# 2019_TFT_Strateasy.net
KiCad netlist of a schematic drawn in Altium Designer
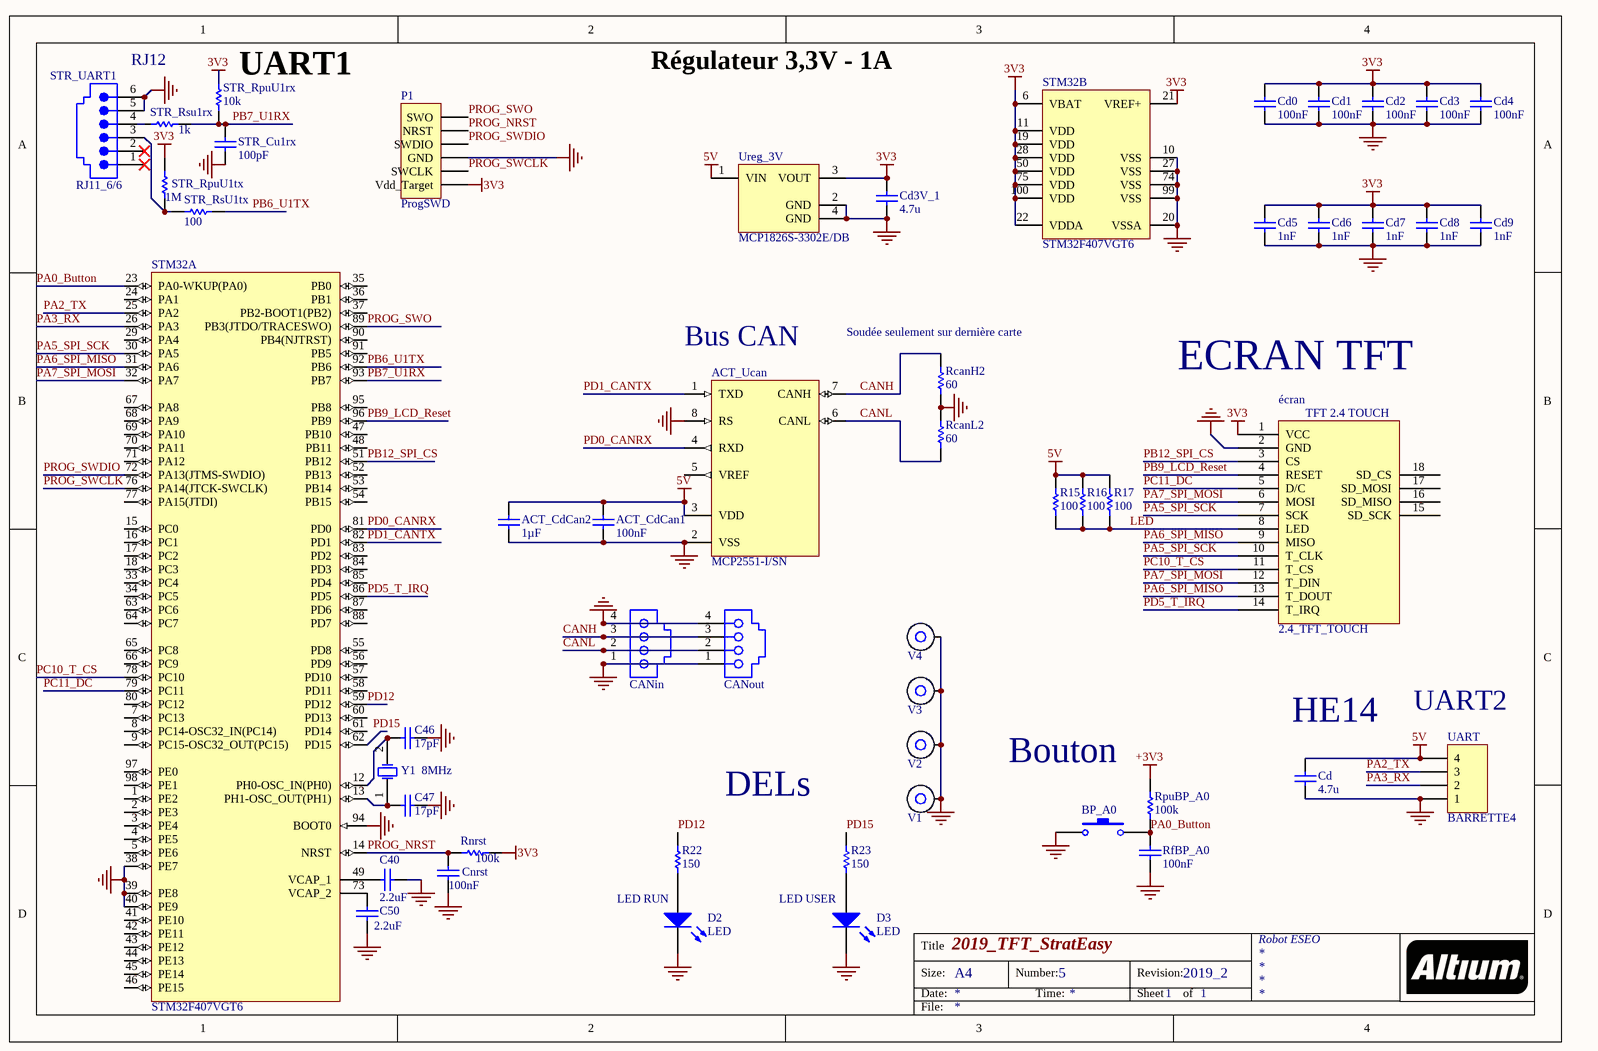
[diagram p0: 2019_TFT_Strateasy.SchDoc, left]
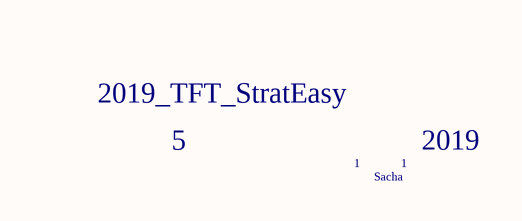
[diagram p1: 2019_TFT_Strateasy.SchDoc, right]

(export (version "E")
  (design (tool "Eeschema 10.0.6"))
  (components
    (comp (ref "ACT_CdCan1")
      (value "100nF")
      (footprint "C0805_N")
      (description "Capacitor")
      (fields (field (name "PUBLISHER") "Altium Limited"))
      (libsource (lib "_ROBOT") (part "Condensateur"))
    )
    (comp (ref "ACT_CdCan2")
      (value "1µF")
      (footprint "C0805_N")
      (description "Capacitor")
      (fields (field (name "PUBLISHER") "Altium Limited"))
      (libsource (lib "_ROBOT") (part "Condensateur"))
    )
    (comp (ref "ACT_Ucan")
      (value "MCP2551-I/SN")
      (footprint "SO8_N")
      (description "High-Speed CAN Transceiver, 8-Pin SOIC, Industrial Temperature")
      (fields (field (name "PUBLISHER") "Damien Guitton"))
      (libsource (lib "Circuit intégré") (part "MCP2551-I/SN"))
    )
    (comp (ref "BP_A0")
      (value "SW_Pushbutton_6x6mm_Vertical")
      (footprint "Switch 6x6 Vertical")
      (description "Switch tactil 6mm x 6mm Vertical")
      (fields (field (name "PUBLISHER") "Damien Guitton"))
      (libsource (lib "_ROBOT") (part "SW_Pushbutton_6x6mm_Vertical"))
    )
    (comp (ref "C40")
      (value "2.2uF")
      (footprint "C0805_N")
      (description "Capacitor")
      (fields (field (name "PUBLISHER") "Altium Limited"))
      (libsource (lib "_ROBOT") (part "Condensateur"))
    )
    (comp (ref "C46")
      (value "17pF")
      (footprint "C0805_N")
      (description "Capacitor")
      (fields (field (name "PUBLISHER") "Altium Limited"))
      (libsource (lib "_ROBOT") (part "Condensateur"))
    )
    (comp (ref "C47")
      (value "17pF")
      (footprint "C0805_N")
      (description "Capacitor")
      (fields (field (name "PUBLISHER") "Altium Limited"))
      (libsource (lib "_ROBOT") (part "Condensateur"))
    )
    (comp (ref "C50")
      (value "2.2uF")
      (footprint "C0805_N")
      (description "Capacitor")
      (fields (field (name "PUBLISHER") "Altium Limited"))
      (libsource (lib "_ROBOT") (part "Condensateur"))
    )
    (comp (ref "CANin")
      (value "634104149621")
      (footprint "634104149621")
      (description "Modular Jack SMT Vertical Plastic 4P4C Top Entry WR-MJ")
      (fields (field (name "PUBLISHER") "Wurth Elektronik"))
      (libsource (lib "ALTIUM-MJ_VERTICAL_PLASTIC") (part "634104149621"))
    )
    (comp (ref "CANout")
      (value "634104149621")
      (footprint "634104149621")
      (description "Modular Jack SMT Vertical Plastic 4P4C Top Entry WR-MJ")
      (fields (field (name "PUBLISHER") "Wurth Elektronik"))
      (libsource (lib "ALTIUM-MJ_VERTICAL_PLASTIC") (part "634104149621"))
    )
    (comp (ref "Cd")
      (value "4.7u")
      (footprint "C0805_N")
      (description "Capacitor")
      (fields (field (name "PUBLISHER") "Altium Limited"))
      (libsource (lib "_ROBOT") (part "Condensateur"))
    )
    (comp (ref "Cd0")
      (value "100nF")
      (footprint "C0805_N")
      (description "Capacitor")
      (fields (field (name "PUBLISHER") "Altium Limited"))
      (libsource (lib "_ROBOT") (part "Condensateur"))
    )
    (comp (ref "Cd1")
      (value "100nF")
      (footprint "C0805_N")
      (description "Capacitor")
      (fields (field (name "PUBLISHER") "Altium Limited"))
      (libsource (lib "_ROBOT") (part "Condensateur"))
    )
    (comp (ref "Cd2")
      (value "100nF")
      (footprint "C0805_N")
      (description "Capacitor")
      (fields (field (name "PUBLISHER") "Altium Limited"))
      (libsource (lib "_ROBOT") (part "Condensateur"))
    )
    (comp (ref "Cd3")
      (value "100nF")
      (footprint "C0805_N")
      (description "Capacitor")
      (fields (field (name "PUBLISHER") "Altium Limited"))
      (libsource (lib "_ROBOT") (part "Condensateur"))
    )
    (comp (ref "Cd3V_1")
      (value "4.7u")
      (footprint "C0805_N")
      (description "Capacitor")
      (fields (field (name "PUBLISHER") "Altium Limited"))
      (libsource (lib "DG_Condensateur") (part "Capacitor"))
    )
    (comp (ref "Cd4")
      (value "100nF")
      (footprint "C0805_N")
      (description "Capacitor")
      (fields (field (name "PUBLISHER") "Altium Limited"))
      (libsource (lib "_ROBOT") (part "Condensateur"))
    )
    (comp (ref "Cd5")
      (value "1nF")
      (footprint "C0805_N")
      (description "Capacitor")
      (fields (field (name "PUBLISHER") "Altium Limited"))
      (libsource (lib "_ROBOT") (part "Condensateur"))
    )
    (comp (ref "Cd6")
      (value "1nF")
      (footprint "C0805_N")
      (description "Capacitor")
      (fields (field (name "PUBLISHER") "Altium Limited"))
      (libsource (lib "_ROBOT") (part "Condensateur"))
    )
    (comp (ref "Cd7")
      (value "1nF")
      (footprint "C0805_N")
      (description "Capacitor")
      (fields (field (name "PUBLISHER") "Altium Limited"))
      (libsource (lib "_ROBOT") (part "Condensateur"))
    )
    (comp (ref "Cd8")
      (value "1nF")
      (footprint "C0805_N")
      (description "Capacitor")
      (fields (field (name "PUBLISHER") "Altium Limited"))
      (libsource (lib "_ROBOT") (part "Condensateur"))
    )
    (comp (ref "Cd9")
      (value "1nF")
      (footprint "C0805_N")
      (description "Capacitor")
      (fields (field (name "PUBLISHER") "Altium Limited"))
      (libsource (lib "_ROBOT") (part "Condensateur"))
    )
    (comp (ref "Cnrst")
      (value "100nF")
      (footprint "C0805_N")
      (description "Capacitor")
      (fields (field (name "PUBLISHER") "Altium Limited"))
      (libsource (lib "_ROBOT") (part "Condensateur"))
    )
    (comp (ref "D2")
      (value "LED")
      (footprint "LED_0805")
      (description "Typical LED")
      (fields (field (name "PUBLISHER") "Altium Limited"))
      (libsource (lib "_ROBOT") (part "LED"))
    )
    (comp (ref "D3")
      (value "LED")
      (footprint "LED_0805")
      (description "Typical LED")
      (fields (field (name "PUBLISHER") "Altium Limited"))
      (libsource (lib "_ROBOT") (part "LED"))
    )
    (comp (ref "P1")
      (value "ProgSWD")
      (footprint "HDR1X6")
      (description "Header, 6-Pin")
      (fields (field (name "PUBLISHER") "Altium Limited"))
      (libsource (lib "DG_Connecteur") (part "Header 6"))
    )
    (comp (ref "R15")
      (value "100")
      (footprint "R1206_N")
      (description "Resistor")
      (fields (field (name "PUBLISHER") "Altium Limited"))
      (libsource (lib "_ROBOT") (part "Resistor"))
    )
    (comp (ref "R16")
      (value "100")
      (footprint "R1206_N")
      (description "Resistor")
      (fields (field (name "PUBLISHER") "Altium Limited"))
      (libsource (lib "_ROBOT") (part "Resistor"))
    )
    (comp (ref "R17")
      (value "100")
      (footprint "R1206_N")
      (description "Resistor")
      (fields (field (name "PUBLISHER") "Altium Limited"))
      (libsource (lib "_ROBOT") (part "Resistor"))
    )
    (comp (ref "R22")
      (value "150")
      (footprint "R1206_N")
      (description "Resistor")
      (fields (field (name "PUBLISHER") "Altium Limited"))
      (libsource (lib "_ROBOT") (part "Resistor"))
    )
    (comp (ref "R23")
      (value "150")
      (footprint "R1206_N")
      (description "Resistor")
      (fields (field (name "PUBLISHER") "Altium Limited"))
      (libsource (lib "_ROBOT") (part "Resistor"))
    )
    (comp (ref "RcanH2")
      (value "60")
      (footprint "R1206_N")
      (description "Resistor")
      (fields (field (name "PUBLISHER") "Altium Limited"))
      (libsource (lib "_ROBOT") (part "Resistor"))
    )
    (comp (ref "RcanL2")
      (value "60")
      (footprint "R1206_N")
      (description "Resistor")
      (fields (field (name "PUBLISHER") "Altium Limited"))
      (libsource (lib "_ROBOT") (part "Resistor"))
    )
    (comp (ref "RfBP_A0")
      (value "100nF")
      (footprint "C0805_N")
      (description "Capacitor")
      (fields (field (name "PUBLISHER") "Altium Limited"))
      (libsource (lib "_ROBOT") (part "Condensateur"))
    )
    (comp (ref "Rnrst")
      (value "100k")
      (footprint "R1206_N")
      (description "Resistor")
      (fields (field (name "PUBLISHER") "Altium Limited"))
      (libsource (lib "_ROBOT") (part "Resistor"))
    )
    (comp (ref "RpuBP_A0")
      (value "100k")
      (footprint "R1206_N")
      (description "Resistor")
      (fields (field (name "PUBLISHER") "Altium Limited"))
      (libsource (lib "_ROBOT") (part "Resistor"))
    )
    (comp (ref "STM32")
      (value "STM32F407VGT6")
      (footprint "STM-LQFP100_N")
      (fields (field (name "MANUFACTURER") "STMicroelectronics"))
      (libsource (lib "STMicroelectronics STM32 F4") (part "STM32F407VGT6"))
    )
    (comp (ref "STR_Cu1rx")
      (value "100pF")
      (footprint "C0805_N")
      (description "Capacitor")
      (fields (field (name "PUBLISHER") "Altium Limited"))
      (libsource (lib "_ROBOT") (part "Condensateur"))
    )
    (comp (ref "STR_RpuU1rx")
      (value "10k")
      (footprint "R1206_N")
      (description "Resistor")
      (fields (field (name "PUBLISHER") "Altium Limited"))
      (libsource (lib "_ROBOT") (part "Resistor"))
    )
    (comp (ref "STR_RpuU1tx")
      (value "1M")
      (footprint "R1206_N")
      (description "Resistor")
      (fields (field (name "PUBLISHER") "Altium Limited"))
      (libsource (lib "_ROBOT") (part "Resistor"))
    )
    (comp (ref "STR_Rsu1rx")
      (value "1k")
      (footprint "R1206_N")
      (description "Resistor")
      (fields (field (name "PUBLISHER") "Altium Limited"))
      (libsource (lib "_ROBOT") (part "Resistor"))
    )
    (comp (ref "STR_RsU1tx")
      (value "100")
      (footprint "R1206_N")
      (description "Resistor")
      (fields (field (name "PUBLISHER") "Altium Limited"))
      (libsource (lib "_ROBOT") (part "Resistor"))
    )
    (comp (ref "STR_UART1")
      (value "RJ11_6/6")
      (footprint "RJ11_6/6 - Wurth Half Shielded Tab Down WR-MJ")
      (description "Right Angle, Standard Profile, Offset Latch DECconnect, Flangeless PCB Jack")
      (fields (field (name "PUBLISHER") "Altium Limited"))
      (libsource (lib "Connecteur") (part "RJ11_6/6"))
    )
    (comp (ref "UART")
      (value "BARRETTE4")
      (footprint "HE14_4")
      (description "Header, 4-Pin")
      (fields (field (name "PUBLISHER") "Altium Limited"))
      (libsource (lib "Connecteur") (part "BARRETTE4"))
    )
    (comp (ref "Ureg_3V")
      (value "MCP1826S-3302E/DB")
      (footprint "SOT223-4N")
      (description "1000 mA, Low Voltage, Low Quiescent Current LDO Regulator, 3-Pin SOT-223, Extended Temperature")
      (fields (field (name "PUBLISHER") "Altium Limited"))
      (libsource (lib "Microchip Power Mgt Line Regulator") (part "MCP1826S-3302E/DB"))
    )
    (comp (ref "V1")
      (value "Entretoise WURTH CMS")
      (footprint "ENTRETOISE_CMS")
      (description "Entretoise Wurth")
      (fields (field (name "PUBLISHER") "Damien Guitton"))
      (libsource (lib "_ROBOT") (part "Entretoise WURTH CMS"))
    )
    (comp (ref "V2")
      (value "Entretoise WURTH CMS")
      (footprint "ENTRETOISE_CMS")
      (description "Entretoise Wurth")
      (fields (field (name "PUBLISHER") "Damien Guitton"))
      (libsource (lib "_ROBOT") (part "Entretoise WURTH CMS"))
    )
    (comp (ref "V3")
      (value "Entretoise WURTH CMS")
      (footprint "ENTRETOISE_CMS")
      (description "Entretoise Wurth")
      (fields (field (name "PUBLISHER") "Damien Guitton"))
      (libsource (lib "_ROBOT") (part "Entretoise WURTH CMS"))
    )
    (comp (ref "V4")
      (value "Entretoise WURTH CMS")
      (footprint "ENTRETOISE_CMS")
      (description "Entretoise Wurth")
      (fields (field (name "PUBLISHER") "Damien Guitton"))
      (libsource (lib "_ROBOT") (part "Entretoise WURTH CMS"))
    )
    (comp (ref "Y1")
      (value "8MHz")
      (footprint "HC49/4H_SMX")
      (description "Crystal Oscillator")
      (fields (field (name "PUBLISHER") "Altium Limited"))
      (libsource (lib "_ROBOT") (part "Quartz"))
    )
    (comp (ref "écran")
      (value "2.4_TFT_TOUCH")
      (footprint "2.4_TFT_TOUCH")
      (libsource (lib "_ROBOT") (part "2.4_TFT_TOUCH"))
    )
  )
  (nets
    (net (code "1") (name "+3V3") (class "Default")
      (node (ref "RpuBP_A0") (pin "1") (pinfunction "1_1") (pintype "passive"))
    )
    (net (code "2") (name "/CANH") (class "Default")
      (node (ref "ACT_Ucan") (pin "7") (pinfunction "CANH_7") (pintype "bidirectional"))
      (node (ref "CANin") (pin "3") (pinfunction "3_3") (pintype "passive"))
      (node (ref "CANout") (pin "3") (pinfunction "3_3") (pintype "passive"))
      (node (ref "RcanH2") (pin "1") (pinfunction "1_1") (pintype "passive"))
    )
    (net (code "3") (name "/CANL") (class "Default")
      (node (ref "ACT_Ucan") (pin "6") (pinfunction "CANL_6") (pintype "bidirectional"))
      (node (ref "CANin") (pin "2") (pinfunction "2_2") (pintype "passive"))
      (node (ref "CANout") (pin "2") (pinfunction "2_2") (pintype "passive"))
      (node (ref "RcanL2") (pin "1") (pinfunction "1_1") (pintype "passive"))
    )
    (net (code "4") (name "/LED") (class "Default")
      (node (ref "R15") (pin "1") (pinfunction "1_1") (pintype "passive"))
      (node (ref "R16") (pin "1") (pinfunction "1_1") (pintype "passive"))
      (node (ref "R17") (pin "1") (pinfunction "1_1") (pintype "passive"))
      (node (ref "écran") (pin "8") (pinfunction "LED_8") (pintype "passive"))
    )
    (net (code "5") (name "/PA0_Button") (class "Default")
      (node (ref "BP_A0") (pin "3") (pinfunction "3_3") (pintype "passive"))
      (node (ref "RfBP_A0") (pin "2") (pinfunction "2_2") (pintype "passive"))
      (node (ref "RpuBP_A0") (pin "2") (pinfunction "2_2") (pintype "passive"))
      (node (ref "STM32") (pin "23") (pinfunction "PA0-WKUP(PA0)_23") (pintype "bidirectional"))
    )
    (net (code "6") (name "/PA2_TX") (class "Default")
      (node (ref "STM32") (pin "25") (pinfunction "PA2_25") (pintype "bidirectional"))
      (node (ref "UART") (pin "3") (pinfunction "3_3") (pintype "passive"))
    )
    (net (code "7") (name "/PA3_RX") (class "Default")
      (node (ref "STM32") (pin "26") (pinfunction "PA3_26") (pintype "bidirectional"))
      (node (ref "UART") (pin "2") (pinfunction "2_2") (pintype "passive"))
    )
    (net (code "8") (name "/PA5_SPI_SCK") (class "Default")
      (node (ref "STM32") (pin "30") (pinfunction "PA5_30") (pintype "bidirectional"))
      (node (ref "écran") (pin "10") (pinfunction "T_CLK_10") (pintype "passive"))
      (node (ref "écran") (pin "7") (pinfunction "SCK_7") (pintype "passive"))
    )
    (net (code "9") (name "/PA6_SPI_MISO") (class "Default")
      (node (ref "STM32") (pin "31") (pinfunction "PA6_31") (pintype "bidirectional"))
      (node (ref "écran") (pin "13") (pinfunction "T_DOUT_13") (pintype "passive"))
      (node (ref "écran") (pin "9") (pinfunction "MISO_9") (pintype "passive"))
    )
    (net (code "10") (name "/PA7_SPI_MOSI") (class "Default")
      (node (ref "STM32") (pin "32") (pinfunction "PA7_32") (pintype "bidirectional"))
      (node (ref "écran") (pin "12") (pinfunction "T_DIN_12") (pintype "passive"))
      (node (ref "écran") (pin "6") (pinfunction "MOSI_6") (pintype "passive"))
    )
    (net (code "11") (name "/PB6_U1TX") (class "Default")
      (node (ref "STM32") (pin "92") (pinfunction "PB6_92") (pintype "bidirectional"))
      (node (ref "STR_RsU1tx") (pin "2") (pinfunction "2_2") (pintype "passive"))
    )
    (net (code "12") (name "/PB7_U1RX") (class "Default")
      (node (ref "STM32") (pin "93") (pinfunction "PB7_93") (pintype "bidirectional"))
      (node (ref "STR_Cu1rx") (pin "2") (pinfunction "2_2") (pintype "passive"))
      (node (ref "STR_RpuU1rx") (pin "1") (pinfunction "1_1") (pintype "passive"))
      (node (ref "STR_Rsu1rx") (pin "1") (pinfunction "1_1") (pintype "passive"))
    )
    (net (code "13") (name "/PB9_LCD_Reset") (class "Default")
      (node (ref "STM32") (pin "96") (pinfunction "PB9_96") (pintype "bidirectional"))
      (node (ref "écran") (pin "4") (pinfunction "RESET_4") (pintype "passive"))
    )
    (net (code "14") (name "/PB12_SPI_CS") (class "Default")
      (node (ref "STM32") (pin "51") (pinfunction "PB12_51") (pintype "bidirectional"))
      (node (ref "écran") (pin "3") (pinfunction "CS_3") (pintype "passive"))
    )
    (net (code "15") (name "/PC10_T_CS") (class "Default")
      (node (ref "STM32") (pin "78") (pinfunction "PC10_78") (pintype "bidirectional"))
      (node (ref "écran") (pin "11") (pinfunction "T_CS_11") (pintype "passive"))
    )
    (net (code "16") (name "/PC11_DC") (class "Default")
      (node (ref "STM32") (pin "79") (pinfunction "PC11_79") (pintype "bidirectional"))
      (node (ref "écran") (pin "5") (pinfunction "D/C_5") (pintype "passive"))
    )
    (net (code "17") (name "/PD0_CANRX") (class "Default")
      (node (ref "ACT_Ucan") (pin "4") (pinfunction "RXD_4") (pintype "output"))
      (node (ref "STM32") (pin "81") (pinfunction "PD0_81") (pintype "bidirectional"))
    )
    (net (code "18") (name "/PD1_CANTX") (class "Default")
      (node (ref "ACT_Ucan") (pin "1") (pinfunction "TXD_1") (pintype "input"))
      (node (ref "STM32") (pin "82") (pinfunction "PD1_82") (pintype "bidirectional"))
    )
    (net (code "19") (name "/PD5_T_IRQ") (class "Default")
      (node (ref "STM32") (pin "86") (pinfunction "PD5_86") (pintype "bidirectional"))
      (node (ref "écran") (pin "14") (pinfunction "T_IRQ_14") (pintype "passive"))
    )
    (net (code "20") (name "/PD12") (class "Default")
      (node (ref "R22") (pin "2") (pinfunction "2_2") (pintype "passive"))
      (node (ref "STM32") (pin "59") (pinfunction "PD12_59") (pintype "bidirectional"))
    )
    (net (code "21") (name "/PD15") (class "Default")
      (node (ref "R23") (pin "2") (pinfunction "2_2") (pintype "passive"))
      (node (ref "STM32") (pin "62") (pinfunction "PD15_62") (pintype "bidirectional"))
    )
    (net (code "22") (name "/PROG_NRST") (class "Default")
      (node (ref "Cnrst") (pin "2") (pinfunction "2_2") (pintype "passive"))
      (node (ref "P1") (pin "5") (pinfunction "NRST_5") (pintype "passive"))
      (node (ref "Rnrst") (pin "1") (pinfunction "1_1") (pintype "passive"))
      (node (ref "STM32") (pin "14") (pinfunction "NRST_14") (pintype "bidirectional"))
    )
    (net (code "23") (name "/PROG_SWCLK") (class "Default")
      (node (ref "P1") (pin "2") (pinfunction "SWCLK_2") (pintype "passive"))
      (node (ref "STM32") (pin "76") (pinfunction "PA14(JTCK-SWCLK)_76") (pintype "bidirectional"))
    )
    (net (code "24") (name "/PROG_SWDIO") (class "Default")
      (node (ref "P1") (pin "4") (pinfunction "SWDIO_4") (pintype "passive"))
      (node (ref "STM32") (pin "72") (pinfunction "PA13(JTMS-SWDIO)_72") (pintype "bidirectional"))
    )
    (net (code "25") (name "/PROG_SWO") (class "Default")
      (node (ref "P1") (pin "6") (pinfunction "SWO_6") (pintype "passive"))
      (node (ref "STM32") (pin "89") (pinfunction "PB3(JTDO/TRACESWO)_89") (pintype "bidirectional"))
    )
    (net (code "26") (name "3V3") (class "Default")
      (node (ref "Cd0") (pin "2") (pinfunction "2_2") (pintype "passive"))
      (node (ref "Cd1") (pin "2") (pinfunction "2_2") (pintype "passive"))
      (node (ref "Cd2") (pin "2") (pinfunction "2_2") (pintype "passive"))
      (node (ref "Cd3") (pin "2") (pinfunction "2_2") (pintype "passive"))
      (node (ref "Cd3V_1") (pin "2") (pinfunction "2_2") (pintype "passive"))
      (node (ref "Cd4") (pin "2") (pinfunction "2_2") (pintype "passive"))
      (node (ref "Cd5") (pin "2") (pinfunction "2_2") (pintype "passive"))
      (node (ref "Cd6") (pin "2") (pinfunction "2_2") (pintype "passive"))
      (node (ref "Cd7") (pin "2") (pinfunction "2_2") (pintype "passive"))
      (node (ref "Cd8") (pin "2") (pinfunction "2_2") (pintype "passive"))
      (node (ref "Cd9") (pin "2") (pinfunction "2_2") (pintype "passive"))
      (node (ref "P1") (pin "1") (pinfunction "Vdd_Target_1") (pintype "passive"))
      (node (ref "Rnrst") (pin "2") (pinfunction "2_2") (pintype "passive"))
      (node (ref "STM32") (pin "100") (pinfunction "VDD_100") (pintype "power_in"))
      (node (ref "STM32") (pin "11") (pinfunction "VDD_11") (pintype "power_in"))
      (node (ref "STM32") (pin "19") (pinfunction "VDD_19") (pintype "power_in"))
      (node (ref "STM32") (pin "21") (pinfunction "VREF+_21") (pintype "power_in"))
      (node (ref "STM32") (pin "22") (pinfunction "VDDA_22") (pintype "power_in"))
      (node (ref "STM32") (pin "28") (pinfunction "VDD_28") (pintype "power_in"))
      (node (ref "STM32") (pin "50") (pinfunction "VDD_50") (pintype "power_in"))
      (node (ref "STM32") (pin "6") (pinfunction "VBAT_6") (pintype "power_in"))
      (node (ref "STM32") (pin "75") (pinfunction "VDD_75") (pintype "power_in"))
      (node (ref "STR_RpuU1rx") (pin "2") (pinfunction "2_2") (pintype "passive"))
      (node (ref "STR_RpuU1tx") (pin "2") (pinfunction "2_2") (pintype "passive"))
      (node (ref "Ureg_3V") (pin "3") (pinfunction "VOUT_3") (pintype "power_in"))
      (node (ref "écran") (pin "1") (pinfunction "VCC_1") (pintype "passive"))
    )
    (net (code "27") (name "5V") (class "Default")
      (node (ref "ACT_CdCan1") (pin "2") (pinfunction "2_2") (pintype "passive"))
      (node (ref "ACT_CdCan2") (pin "2") (pinfunction "2_2") (pintype "passive"))
      (node (ref "ACT_Ucan") (pin "3") (pinfunction "VDD_3") (pintype "power_in"))
      (node (ref "Cd") (pin "2") (pinfunction "2_2") (pintype "passive"))
      (node (ref "R15") (pin "2") (pinfunction "2_2") (pintype "passive"))
      (node (ref "R16") (pin "2") (pinfunction "2_2") (pintype "passive"))
      (node (ref "R17") (pin "2") (pinfunction "2_2") (pintype "passive"))
      (node (ref "UART") (pin "4") (pinfunction "4_4") (pintype "passive"))
      (node (ref "Ureg_3V") (pin "1") (pinfunction "VIN_1") (pintype "power_in"))
    )
    (net (code "28") (name "GND") (class "Default")
      (node (ref "ACT_CdCan1") (pin "1") (pinfunction "1_1") (pintype "passive"))
      (node (ref "ACT_CdCan2") (pin "1") (pinfunction "1_1") (pintype "passive"))
      (node (ref "ACT_Ucan") (pin "2") (pinfunction "VSS_2") (pintype "power_in"))
      (node (ref "ACT_Ucan") (pin "8") (pinfunction "RS_8") (pintype "input"))
      (node (ref "BP_A0") (pin "1") (pinfunction "1_1") (pintype "passive"))
      (node (ref "C40") (pin "1") (pinfunction "1_1") (pintype "passive"))
      (node (ref "C46") (pin "1") (pinfunction "1_1") (pintype "passive"))
      (node (ref "C47") (pin "1") (pinfunction "1_1") (pintype "passive"))
      (node (ref "C50") (pin "1") (pinfunction "1_1") (pintype "passive"))
      (node (ref "CANin") (pin "1") (pinfunction "1_1") (pintype "passive"))
      (node (ref "CANin") (pin "4") (pinfunction "4_4") (pintype "passive"))
      (node (ref "CANout") (pin "1") (pinfunction "1_1") (pintype "passive"))
      (node (ref "CANout") (pin "4") (pinfunction "4_4") (pintype "passive"))
      (node (ref "Cd") (pin "1") (pinfunction "1_1") (pintype "passive"))
      (node (ref "Cd0") (pin "1") (pinfunction "1_1") (pintype "passive"))
      (node (ref "Cd1") (pin "1") (pinfunction "1_1") (pintype "passive"))
      (node (ref "Cd2") (pin "1") (pinfunction "1_1") (pintype "passive"))
      (node (ref "Cd3") (pin "1") (pinfunction "1_1") (pintype "passive"))
      (node (ref "Cd3V_1") (pin "1") (pinfunction "1_1") (pintype "passive"))
      (node (ref "Cd4") (pin "1") (pinfunction "1_1") (pintype "passive"))
      (node (ref "Cd5") (pin "1") (pinfunction "1_1") (pintype "passive"))
      (node (ref "Cd6") (pin "1") (pinfunction "1_1") (pintype "passive"))
      (node (ref "Cd7") (pin "1") (pinfunction "1_1") (pintype "passive"))
      (node (ref "Cd8") (pin "1") (pinfunction "1_1") (pintype "passive"))
      (node (ref "Cd9") (pin "1") (pinfunction "1_1") (pintype "passive"))
      (node (ref "Cnrst") (pin "1") (pinfunction "1_1") (pintype "passive"))
      (node (ref "D2") (pin "2") (pinfunction "K_2") (pintype "passive"))
      (node (ref "D3") (pin "2") (pinfunction "K_2") (pintype "passive"))
      (node (ref "P1") (pin "3") (pinfunction "GND_3") (pintype "passive"))
      (node (ref "RcanH2") (pin "2") (pinfunction "2_2") (pintype "passive"))
      (node (ref "RcanL2") (pin "2") (pinfunction "2_2") (pintype "passive"))
      (node (ref "RfBP_A0") (pin "1") (pinfunction "1_1") (pintype "passive"))
      (node (ref "STM32") (pin "10") (pinfunction "VSS_10") (pintype "power_in"))
      (node (ref "STM32") (pin "20") (pinfunction "VSSA_20") (pintype "power_in"))
      (node (ref "STM32") (pin "27") (pinfunction "VSS_27") (pintype "power_in"))
      (node (ref "STM32") (pin "38") (pinfunction "PE7_38") (pintype "bidirectional"))
      (node (ref "STM32") (pin "39") (pinfunction "PE8_39") (pintype "bidirectional"))
      (node (ref "STM32") (pin "40") (pinfunction "PE9_40") (pintype "bidirectional"))
      (node (ref "STM32") (pin "74") (pinfunction "VSS_74") (pintype "power_in"))
      (node (ref "STM32") (pin "94") (pinfunction "BOOT0_94") (pintype "input"))
      (node (ref "STM32") (pin "99") (pinfunction "VSS_99") (pintype "power_in"))
      (node (ref "STR_Cu1rx") (pin "1") (pinfunction "1_1") (pintype "passive"))
      (node (ref "STR_UART1") (pin "5") (pinfunction "5_5") (pintype "passive"))
      (node (ref "STR_UART1") (pin "6") (pinfunction "6_6") (pintype "passive"))
      (node (ref "UART") (pin "1") (pinfunction "1_1") (pintype "passive"))
      (node (ref "Ureg_3V") (pin "2") (pinfunction "GND_2") (pintype "power_in"))
      (node (ref "Ureg_3V") (pin "4") (pinfunction "GND_4") (pintype "power_in"))
      (node (ref "V1") (pin "1") (pinfunction "1_1") (pintype "passive"))
      (node (ref "V2") (pin "1") (pinfunction "1_1") (pintype "passive"))
      (node (ref "V3") (pin "1") (pinfunction "1_1") (pintype "passive"))
      (node (ref "V4") (pin "1") (pinfunction "1_1") (pintype "passive"))
      (node (ref "écran") (pin "2") (pinfunction "GND_2") (pintype "passive"))
    )
    (net (code "29") (name "Net-(D2-A)") (class "Default")
      (node (ref "D2") (pin "1") (pinfunction "A_1") (pintype "passive"))
      (node (ref "R22") (pin "1") (pinfunction "1_1") (pintype "passive"))
    )
    (net (code "30") (name "Net-(D3-A)") (class "Default")
      (node (ref "D3") (pin "1") (pinfunction "A_1") (pintype "passive"))
      (node (ref "R23") (pin "1") (pinfunction "1_1") (pintype "passive"))
    )
    (net (code "31") (name "Net-(STM32A-PH0-OSC_IN(PH0))") (class "Default")
      (node (ref "C46") (pin "2") (pinfunction "2_2") (pintype "passive"))
      (node (ref "STM32") (pin "12") (pinfunction "PH0-OSC_IN(PH0)_12") (pintype "bidirectional"))
      (node (ref "Y1") (pin "2") (pinfunction "OSC2_2") (pintype "passive"))
    )
    (net (code "32") (name "Net-(STM32A-PH1-OSC_OUT(PH1))") (class "Default")
      (node (ref "C47") (pin "2") (pinfunction "2_2") (pintype "passive"))
      (node (ref "STM32") (pin "13") (pinfunction "PH1-OSC_OUT(PH1)_13") (pintype "bidirectional"))
      (node (ref "Y1") (pin "1") (pinfunction "OSC1_1") (pintype "passive"))
    )
    (net (code "33") (name "Net-(STM32A-VCAP_1)") (class "Default")
      (node (ref "C40") (pin "2") (pinfunction "2_2") (pintype "passive"))
      (node (ref "STM32") (pin "49") (pinfunction "VCAP_1_49") (pintype "power_in"))
    )
    (net (code "34") (name "Net-(STM32A-VCAP_2)") (class "Default")
      (node (ref "C50") (pin "2") (pinfunction "2_2") (pintype "passive"))
      (node (ref "STM32") (pin "73") (pinfunction "VCAP_2_73") (pintype "power_in"))
    )
    (net (code "35") (name "Net-(STR_RpuU1tx-Pad1)") (class "Default")
      (node (ref "STR_RpuU1tx") (pin "1") (pinfunction "1_1") (pintype "passive"))
      (node (ref "STR_RsU1tx") (pin "1") (pinfunction "1_1") (pintype "passive"))
      (node (ref "STR_UART1") (pin "3") (pinfunction "3_3") (pintype "passive"))
    )
    (net (code "36") (name "Net-(STR_Rsu1rx-Pad2)") (class "Default")
      (node (ref "STR_Rsu1rx") (pin "2") (pinfunction "2_2") (pintype "passive"))
      (node (ref "STR_UART1") (pin "4") (pinfunction "4_4") (pintype "passive"))
    )
    (net (code "37") (name "unconnected-(ACT_Ucan-VREF-Pad5)") (class "Default")
      (node (ref "ACT_Ucan") (pin "5") (pinfunction "VREF_5") (pintype "output"))
    )
    (net (code "38") (name "unconnected-(STM32A-PA1-Pad24)") (class "Default")
      (node (ref "STM32") (pin "24") (pinfunction "PA1_24") (pintype "bidirectional"))
    )
    (net (code "39") (name "unconnected-(STM32A-PA4-Pad29)") (class "Default")
      (node (ref "STM32") (pin "29") (pinfunction "PA4_29") (pintype "bidirectional"))
    )
    (net (code "40") (name "unconnected-(STM32A-PA8-Pad67)") (class "Default")
      (node (ref "STM32") (pin "67") (pinfunction "PA8_67") (pintype "bidirectional"))
    )
    (net (code "41") (name "unconnected-(STM32A-PA9-Pad68)") (class "Default")
      (node (ref "STM32") (pin "68") (pinfunction "PA9_68") (pintype "bidirectional"))
    )
    (net (code "42") (name "unconnected-(STM32A-PA10-Pad69)") (class "Default")
      (node (ref "STM32") (pin "69") (pinfunction "PA10_69") (pintype "bidirectional"))
    )
    (net (code "43") (name "unconnected-(STM32A-PA11-Pad70)") (class "Default")
      (node (ref "STM32") (pin "70") (pinfunction "PA11_70") (pintype "bidirectional"))
    )
    (net (code "44") (name "unconnected-(STM32A-PA12-Pad71)") (class "Default")
      (node (ref "STM32") (pin "71") (pinfunction "PA12_71") (pintype "bidirectional"))
    )
    (net (code "45") (name "unconnected-(STM32A-PA15(JTDI)-Pad77)") (class "Default")
      (node (ref "STM32") (pin "77") (pinfunction "PA15(JTDI)_77") (pintype "bidirectional"))
    )
    (net (code "46") (name "unconnected-(STM32A-PB0-Pad35)") (class "Default")
      (node (ref "STM32") (pin "35") (pinfunction "PB0_35") (pintype "bidirectional"))
    )
    (net (code "47") (name "unconnected-(STM32A-PB1-Pad36)") (class "Default")
      (node (ref "STM32") (pin "36") (pinfunction "PB1_36") (pintype "bidirectional"))
    )
    (net (code "48") (name "unconnected-(STM32A-PB2-BOOT1(PB2)-Pad37)") (class "Default")
      (node (ref "STM32") (pin "37") (pinfunction "PB2-BOOT1(PB2)_37") (pintype "bidirectional"))
    )
    (net (code "49") (name "unconnected-(STM32A-PB4(NJTRST)-Pad90)") (class "Default")
      (node (ref "STM32") (pin "90") (pinfunction "PB4(NJTRST)_90") (pintype "bidirectional"))
    )
    (net (code "50") (name "unconnected-(STM32A-PB5-Pad91)") (class "Default")
      (node (ref "STM32") (pin "91") (pinfunction "PB5_91") (pintype "bidirectional"))
    )
    (net (code "51") (name "unconnected-(STM32A-PB8-Pad95)") (class "Default")
      (node (ref "STM32") (pin "95") (pinfunction "PB8_95") (pintype "bidirectional"))
    )
    (net (code "52") (name "unconnected-(STM32A-PB10-Pad47)") (class "Default")
      (node (ref "STM32") (pin "47") (pinfunction "PB10_47") (pintype "bidirectional"))
    )
    (net (code "53") (name "unconnected-(STM32A-PB11-Pad48)") (class "Default")
      (node (ref "STM32") (pin "48") (pinfunction "PB11_48") (pintype "bidirectional"))
    )
    (net (code "54") (name "unconnected-(STM32A-PB13-Pad52)") (class "Default")
      (node (ref "STM32") (pin "52") (pinfunction "PB13_52") (pintype "bidirectional"))
    )
    (net (code "55") (name "unconnected-(STM32A-PB14-Pad53)") (class "Default")
      (node (ref "STM32") (pin "53") (pinfunction "PB14_53") (pintype "bidirectional"))
    )
    (net (code "56") (name "unconnected-(STM32A-PB15-Pad54)") (class "Default")
      (node (ref "STM32") (pin "54") (pinfunction "PB15_54") (pintype "bidirectional"))
    )
    (net (code "57") (name "unconnected-(STM32A-PC0-Pad15)") (class "Default")
      (node (ref "STM32") (pin "15") (pinfunction "PC0_15") (pintype "bidirectional"))
    )
    (net (code "58") (name "unconnected-(STM32A-PC1-Pad16)") (class "Default")
      (node (ref "STM32") (pin "16") (pinfunction "PC1_16") (pintype "bidirectional"))
    )
    (net (code "59") (name "unconnected-(STM32A-PC2-Pad17)") (class "Default")
      (node (ref "STM32") (pin "17") (pinfunction "PC2_17") (pintype "bidirectional"))
    )
    (net (code "60") (name "unconnected-(STM32A-PC3-Pad18)") (class "Default")
      (node (ref "STM32") (pin "18") (pinfunction "PC3_18") (pintype "bidirectional"))
    )
    (net (code "61") (name "unconnected-(STM32A-PC4-Pad33)") (class "Default")
      (node (ref "STM32") (pin "33") (pinfunction "PC4_33") (pintype "bidirectional"))
    )
    (net (code "62") (name "unconnected-(STM32A-PC5-Pad34)") (class "Default")
      (node (ref "STM32") (pin "34") (pinfunction "PC5_34") (pintype "bidirectional"))
    )
    (net (code "63") (name "unconnected-(STM32A-PC6-Pad63)") (class "Default")
      (node (ref "STM32") (pin "63") (pinfunction "PC6_63") (pintype "bidirectional"))
    )
    (net (code "64") (name "unconnected-(STM32A-PC7-Pad64)") (class "Default")
      (node (ref "STM32") (pin "64") (pinfunction "PC7_64") (pintype "bidirectional"))
    )
    (net (code "65") (name "unconnected-(STM32A-PC8-Pad65)") (class "Default")
      (node (ref "STM32") (pin "65") (pinfunction "PC8_65") (pintype "bidirectional"))
    )
    (net (code "66") (name "unconnected-(STM32A-PC9-Pad66)") (class "Default")
      (node (ref "STM32") (pin "66") (pinfunction "PC9_66") (pintype "bidirectional"))
    )
    (net (code "67") (name "unconnected-(STM32A-PC12-Pad80)") (class "Default")
      (node (ref "STM32") (pin "80") (pinfunction "PC12_80") (pintype "bidirectional"))
    )
    (net (code "68") (name "unconnected-(STM32A-PC13-Pad7)") (class "Default")
      (node (ref "STM32") (pin "7") (pinfunction "PC13_7") (pintype "bidirectional"))
    )
    (net (code "69") (name "unconnected-(STM32A-PC14-OSC32_IN(PC14)-Pad8)") (class "Default")
      (node (ref "STM32") (pin "8") (pinfunction "PC14-OSC32_IN(PC14)_8") (pintype "bidirectional"))
    )
    (net (code "70") (name "unconnected-(STM32A-PC15-OSC32_OUT(PC15)-Pad9)") (class "Default")
      (node (ref "STM32") (pin "9") (pinfunction "PC15-OSC32_OUT(PC15)_9") (pintype "bidirectional"))
    )
    (net (code "71") (name "unconnected-(STM32A-PD2-Pad83)") (class "Default")
      (node (ref "STM32") (pin "83") (pinfunction "PD2_83") (pintype "bidirectional"))
    )
    (net (code "72") (name "unconnected-(STM32A-PD3-Pad84)") (class "Default")
      (node (ref "STM32") (pin "84") (pinfunction "PD3_84") (pintype "bidirectional"))
    )
    (net (code "73") (name "unconnected-(STM32A-PD4-Pad85)") (class "Default")
      (node (ref "STM32") (pin "85") (pinfunction "PD4_85") (pintype "bidirectional"))
    )
    (net (code "74") (name "unconnected-(STM32A-PD6-Pad87)") (class "Default")
      (node (ref "STM32") (pin "87") (pinfunction "PD6_87") (pintype "bidirectional"))
    )
    (net (code "75") (name "unconnected-(STM32A-PD7-Pad88)") (class "Default")
      (node (ref "STM32") (pin "88") (pinfunction "PD7_88") (pintype "bidirectional"))
    )
    (net (code "76") (name "unconnected-(STM32A-PD8-Pad55)") (class "Default")
      (node (ref "STM32") (pin "55") (pinfunction "PD8_55") (pintype "bidirectional"))
    )
    (net (code "77") (name "unconnected-(STM32A-PD9-Pad56)") (class "Default")
      (node (ref "STM32") (pin "56") (pinfunction "PD9_56") (pintype "bidirectional"))
    )
    (net (code "78") (name "unconnected-(STM32A-PD10-Pad57)") (class "Default")
      (node (ref "STM32") (pin "57") (pinfunction "PD10_57") (pintype "bidirectional"))
    )
    (net (code "79") (name "unconnected-(STM32A-PD11-Pad58)") (class "Default")
      (node (ref "STM32") (pin "58") (pinfunction "PD11_58") (pintype "bidirectional"))
    )
    (net (code "80") (name "unconnected-(STM32A-PD13-Pad60)") (class "Default")
      (node (ref "STM32") (pin "60") (pinfunction "PD13_60") (pintype "bidirectional"))
    )
    (net (code "81") (name "unconnected-(STM32A-PD14-Pad61)") (class "Default")
      (node (ref "STM32") (pin "61") (pinfunction "PD14_61") (pintype "bidirectional"))
    )
    (net (code "82") (name "unconnected-(STM32A-PE0-Pad97)") (class "Default")
      (node (ref "STM32") (pin "97") (pinfunction "PE0_97") (pintype "bidirectional"))
    )
    (net (code "83") (name "unconnected-(STM32A-PE1-Pad98)") (class "Default")
      (node (ref "STM32") (pin "98") (pinfunction "PE1_98") (pintype "bidirectional"))
    )
    (net (code "84") (name "unconnected-(STM32A-PE2-Pad1)") (class "Default")
      (node (ref "STM32") (pin "1") (pinfunction "PE2_1") (pintype "bidirectional"))
    )
    (net (code "85") (name "unconnected-(STM32A-PE3-Pad2)") (class "Default")
      (node (ref "STM32") (pin "2") (pinfunction "PE3_2") (pintype "bidirectional"))
    )
    (net (code "86") (name "unconnected-(STM32A-PE4-Pad3)") (class "Default")
      (node (ref "STM32") (pin "3") (pinfunction "PE4_3") (pintype "bidirectional"))
    )
    (net (code "87") (name "unconnected-(STM32A-PE5-Pad4)") (class "Default")
      (node (ref "STM32") (pin "4") (pinfunction "PE5_4") (pintype "bidirectional"))
    )
    (net (code "88") (name "unconnected-(STM32A-PE6-Pad5)") (class "Default")
      (node (ref "STM32") (pin "5") (pinfunction "PE6_5") (pintype "bidirectional"))
    )
    (net (code "89") (name "unconnected-(STM32A-PE10-Pad41)") (class "Default")
      (node (ref "STM32") (pin "41") (pinfunction "PE10_41") (pintype "bidirectional"))
    )
    (net (code "90") (name "unconnected-(STM32A-PE11-Pad42)") (class "Default")
      (node (ref "STM32") (pin "42") (pinfunction "PE11_42") (pintype "bidirectional"))
    )
    (net (code "91") (name "unconnected-(STM32A-PE12-Pad43)") (class "Default")
      (node (ref "STM32") (pin "43") (pinfunction "PE12_43") (pintype "bidirectional"))
    )
    (net (code "92") (name "unconnected-(STM32A-PE13-Pad44)") (class "Default")
      (node (ref "STM32") (pin "44") (pinfunction "PE13_44") (pintype "bidirectional"))
    )
    (net (code "93") (name "unconnected-(STM32A-PE14-Pad45)") (class "Default")
      (node (ref "STM32") (pin "45") (pinfunction "PE14_45") (pintype "bidirectional"))
    )
    (net (code "94") (name "unconnected-(STM32A-PE15-Pad46)") (class "Default")
      (node (ref "STM32") (pin "46") (pinfunction "PE15_46") (pintype "bidirectional"))
    )
    (net (code "95") (name "unconnected-(STR_UART1-Pad1)") (class "Default")
      (node (ref "STR_UART1") (pin "1") (pinfunction "1_1") (pintype "passive+no_connect"))
    )
    (net (code "96") (name "unconnected-(STR_UART1-Pad2)") (class "Default")
      (node (ref "STR_UART1") (pin "2") (pinfunction "2_2") (pintype "passive+no_connect"))
    )
    (net (code "97") (name "unconnected-(écran-SD_CS-Pad18)") (class "Default")
      (node (ref "écran") (pin "18") (pinfunction "SD_CS_18") (pintype "passive"))
    )
    (net (code "98") (name "unconnected-(écran-SD_MISO-Pad16)") (class "Default")
      (node (ref "écran") (pin "16") (pinfunction "SD_MISO_16") (pintype "passive"))
    )
    (net (code "99") (name "unconnected-(écran-SD_MOSI-Pad17)") (class "Default")
      (node (ref "écran") (pin "17") (pinfunction "SD_MOSI_17") (pintype "passive"))
    )
    (net (code "100") (name "unconnected-(écran-SD_SCK-Pad15)") (class "Default")
      (node (ref "écran") (pin "15") (pinfunction "SD_SCK_15") (pintype "passive"))
    )
  )
)
